# IrDA_TFDU6102.net
KiCad netlist of a schematic drawn in Altium Designer
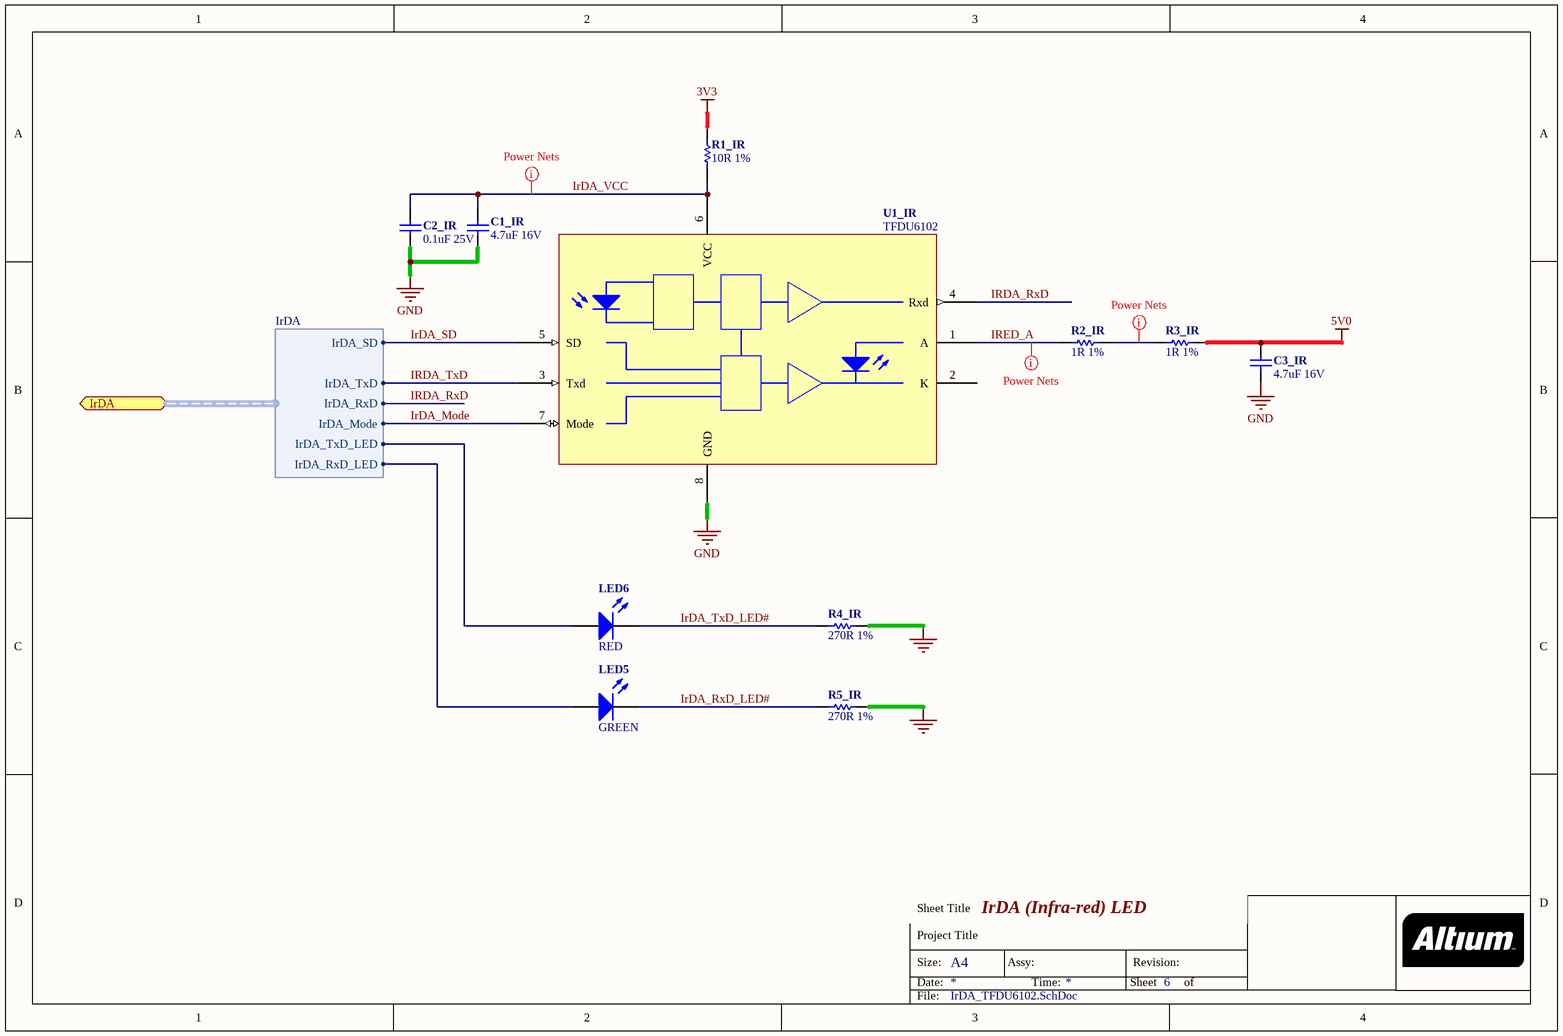
[diagram p0: IrDA_TFDU6102.SchDoc]

(export (version "E")
  (design (tool "Eeschema 10.0.6"))
  (components
    (comp (ref "C1_IR")
      (value "4.7uF 16V")
      (footprint "CAPC2012-STAR")
      (description "Capacitor, Ceramic, 4.7uF 10% 16V 0805 (2012) X7R")
      (fields (field (name "TOLERANCE") "10 %"))
      (libsource (lib "AltiumDesignLibrary") (part "CAP-NP"))
    )
    (comp (ref "C2_IR")
      (value "0.1uF 25V")
      (footprint "CAPC1005-STAR")
      (description "Capacitor, Ceramic, 0.1uF 25V 0402 (1005)")
      (fields (field (name "TOLERANCE") "10 %"))
      (libsource (lib "AltiumDesignLibrary") (part "CAP-NP"))
    )
    (comp (ref "C3_IR")
      (value "4.7uF 16V")
      (footprint "CAPC2012-STAR")
      (description "Capacitor, Ceramic, 4.7uF 10% 16V 0805 (2012) X7R")
      (fields (field (name "TOLERANCE") "10 %"))
      (libsource (lib "AltiumDesignLibrary") (part "CAP-NP"))
    )
    (comp (ref "LED5")
      (value "GREEN")
      (footprint "LED2012-STAR")
      (description "LED, Green 0805 (2012) KP-2012SGD")
      (libsource (lib "AltiumDesignLibrary") (part "DIO-LED-1S"))
    )
    (comp (ref "LED6")
      (value "RED")
      (footprint "LED2012-STAR")
      (description "LED, Red 0805 (2013) HSMH-C170")
      (libsource (lib "AltiumDesignLibrary") (part "DIO-LED-1S"))
    )
    (comp (ref "R1_IR")
      (value "10R 1%")
      (footprint "RESC2012-STAR")
      (description "Resistor, 10R 1% 0805 (2012)")
      (fields (field (name "TOLERANCE") "1 %"))
      (libsource (lib "AltiumDesignLibrary") (part "RES"))
    )
    (comp (ref "R2_IR")
      (value "1R 1%")
      (footprint "RESC2012-STAR")
      (description "Resistor, 1R 1% 0805 (2012)")
      (fields (field (name "TOLERANCE") "1 %"))
      (libsource (lib "AltiumDesignLibrary") (part "RES"))
    )
    (comp (ref "R3_IR")
      (value "1R 1%")
      (footprint "RESC2012-STAR")
      (description "Resistor, 1R 1% 0805 (2012)")
      (fields (field (name "TOLERANCE") "1 %"))
      (libsource (lib "AltiumDesignLibrary") (part "RES"))
    )
    (comp (ref "R4_IR")
      (value "270R 1%")
      (footprint "RESC1005-STAR")
      (description "Resistor, 270R 1% 0402 (1005)")
      (fields (field (name "TOLERANCE") "1 %"))
      (libsource (lib "AltiumDesignLibrary") (part "RES"))
    )
    (comp (ref "R5_IR")
      (value "270R 1%")
      (footprint "RESC1005-STAR")
      (description "Resistor, 270R 1% 0402 (1005)")
      (fields (field (name "TOLERANCE") "1 %"))
      (libsource (lib "AltiumDesignLibrary") (part "RES"))
    )
    (comp (ref "U1_IR")
      (value "TFDU6102")
      (footprint "TFDU6102")
      (description "LED, TFDU6102 Infrared Transceiver up to 4Mbits/s")
      (libsource (lib "AltiumDesignLibrary") (part "TFDU6102"))
    )
  )
  (nets
    (net (code "2") (name "/IRDA_RxD") (class "Default")
      (node (ref "U1_IR") (pin "4") (pinfunction "Rxd_4") (pintype "output"))
    )
    (net (code "3") (name "/IRDA_TxD") (class "Default")
      (node (ref "U1_IR") (pin "3") (pinfunction "Txd_3") (pintype "input"))
    )
    (net (code "4") (name "/IRED_A") (class "Default")
      (node (ref "R2_IR") (pin "1") (pinfunction "1_1") (pintype "passive"))
      (node (ref "U1_IR") (pin "1") (pinfunction "A_1") (pintype "power_in"))
    )
    (net (code "5") (name "/IrDA_Mode") (class "Default")
      (node (ref "U1_IR") (pin "7") (pinfunction "Mode_7") (pintype "bidirectional"))
    )
    (net (code "6") (name "/IrDA_RxD_LED") (class "Default")
      (node (ref "LED5") (pin "1") (pinfunction "A_1") (pintype "passive"))
    )
    (net (code "7") (name "/IrDA_RxD_LED#") (class "Default")
      (node (ref "LED5") (pin "2") (pinfunction "K_2") (pintype "passive"))
      (node (ref "R5_IR") (pin "2") (pinfunction "2_2") (pintype "passive"))
    )
    (net (code "8") (name "/IrDA_SD") (class "Default")
      (node (ref "U1_IR") (pin "5") (pinfunction "SD_5") (pintype "input"))
    )
    (net (code "9") (name "/IrDA_TxD_LED") (class "Default")
      (node (ref "LED6") (pin "1") (pinfunction "A_1") (pintype "passive"))
    )
    (net (code "10") (name "/IrDA_TxD_LED#") (class "Default")
      (node (ref "LED6") (pin "2") (pinfunction "K_2") (pintype "passive"))
      (node (ref "R4_IR") (pin "2") (pinfunction "2_2") (pintype "passive"))
    )
    (net (code "11") (name "/IrDA_VCC") (class "Default")
      (node (ref "C1_IR") (pin "1") (pinfunction "1_1") (pintype "passive"))
      (node (ref "C2_IR") (pin "1") (pinfunction "1_1") (pintype "passive"))
      (node (ref "R1_IR") (pin "1") (pinfunction "1_1") (pintype "passive"))
      (node (ref "U1_IR") (pin "6") (pinfunction "VCC_6") (pintype "power_in"))
    )
    (net (code "13") (name "3V3") (class "Default")
      (node (ref "R1_IR") (pin "2") (pinfunction "2_2") (pintype "passive"))
    )
    (net (code "14") (name "5V0") (class "Default")
      (node (ref "C3_IR") (pin "1") (pinfunction "1_1") (pintype "passive"))
      (node (ref "R3_IR") (pin "2") (pinfunction "2_2") (pintype "passive"))
    )
    (net (code "15") (name "GND") (class "Default")
      (node (ref "C1_IR") (pin "2") (pinfunction "2_2") (pintype "passive"))
      (node (ref "C2_IR") (pin "2") (pinfunction "2_2") (pintype "passive"))
      (node (ref "C3_IR") (pin "2") (pinfunction "2_2") (pintype "passive"))
      (node (ref "R4_IR") (pin "1") (pinfunction "1_1") (pintype "passive"))
      (node (ref "R5_IR") (pin "1") (pinfunction "1_1") (pintype "passive"))
      (node (ref "U1_IR") (pin "8") (pinfunction "GND_8") (pintype "power_in"))
    )
    (net (code "16") (name "Net-(R2_IR-Pad2)") (class "Default")
      (node (ref "R2_IR") (pin "2") (pinfunction "2_2") (pintype "passive"))
      (node (ref "R3_IR") (pin "1") (pinfunction "1_1") (pintype "passive"))
    )
    (net (code "17") (name "unconnected-(U1_IR-K-Pad2)") (class "Default")
      (node (ref "U1_IR") (pin "2") (pinfunction "K_2") (pintype "passive"))
    )
  )
)
